# Sheet1.net
KiCad netlist of a schematic drawn in Altium Designer
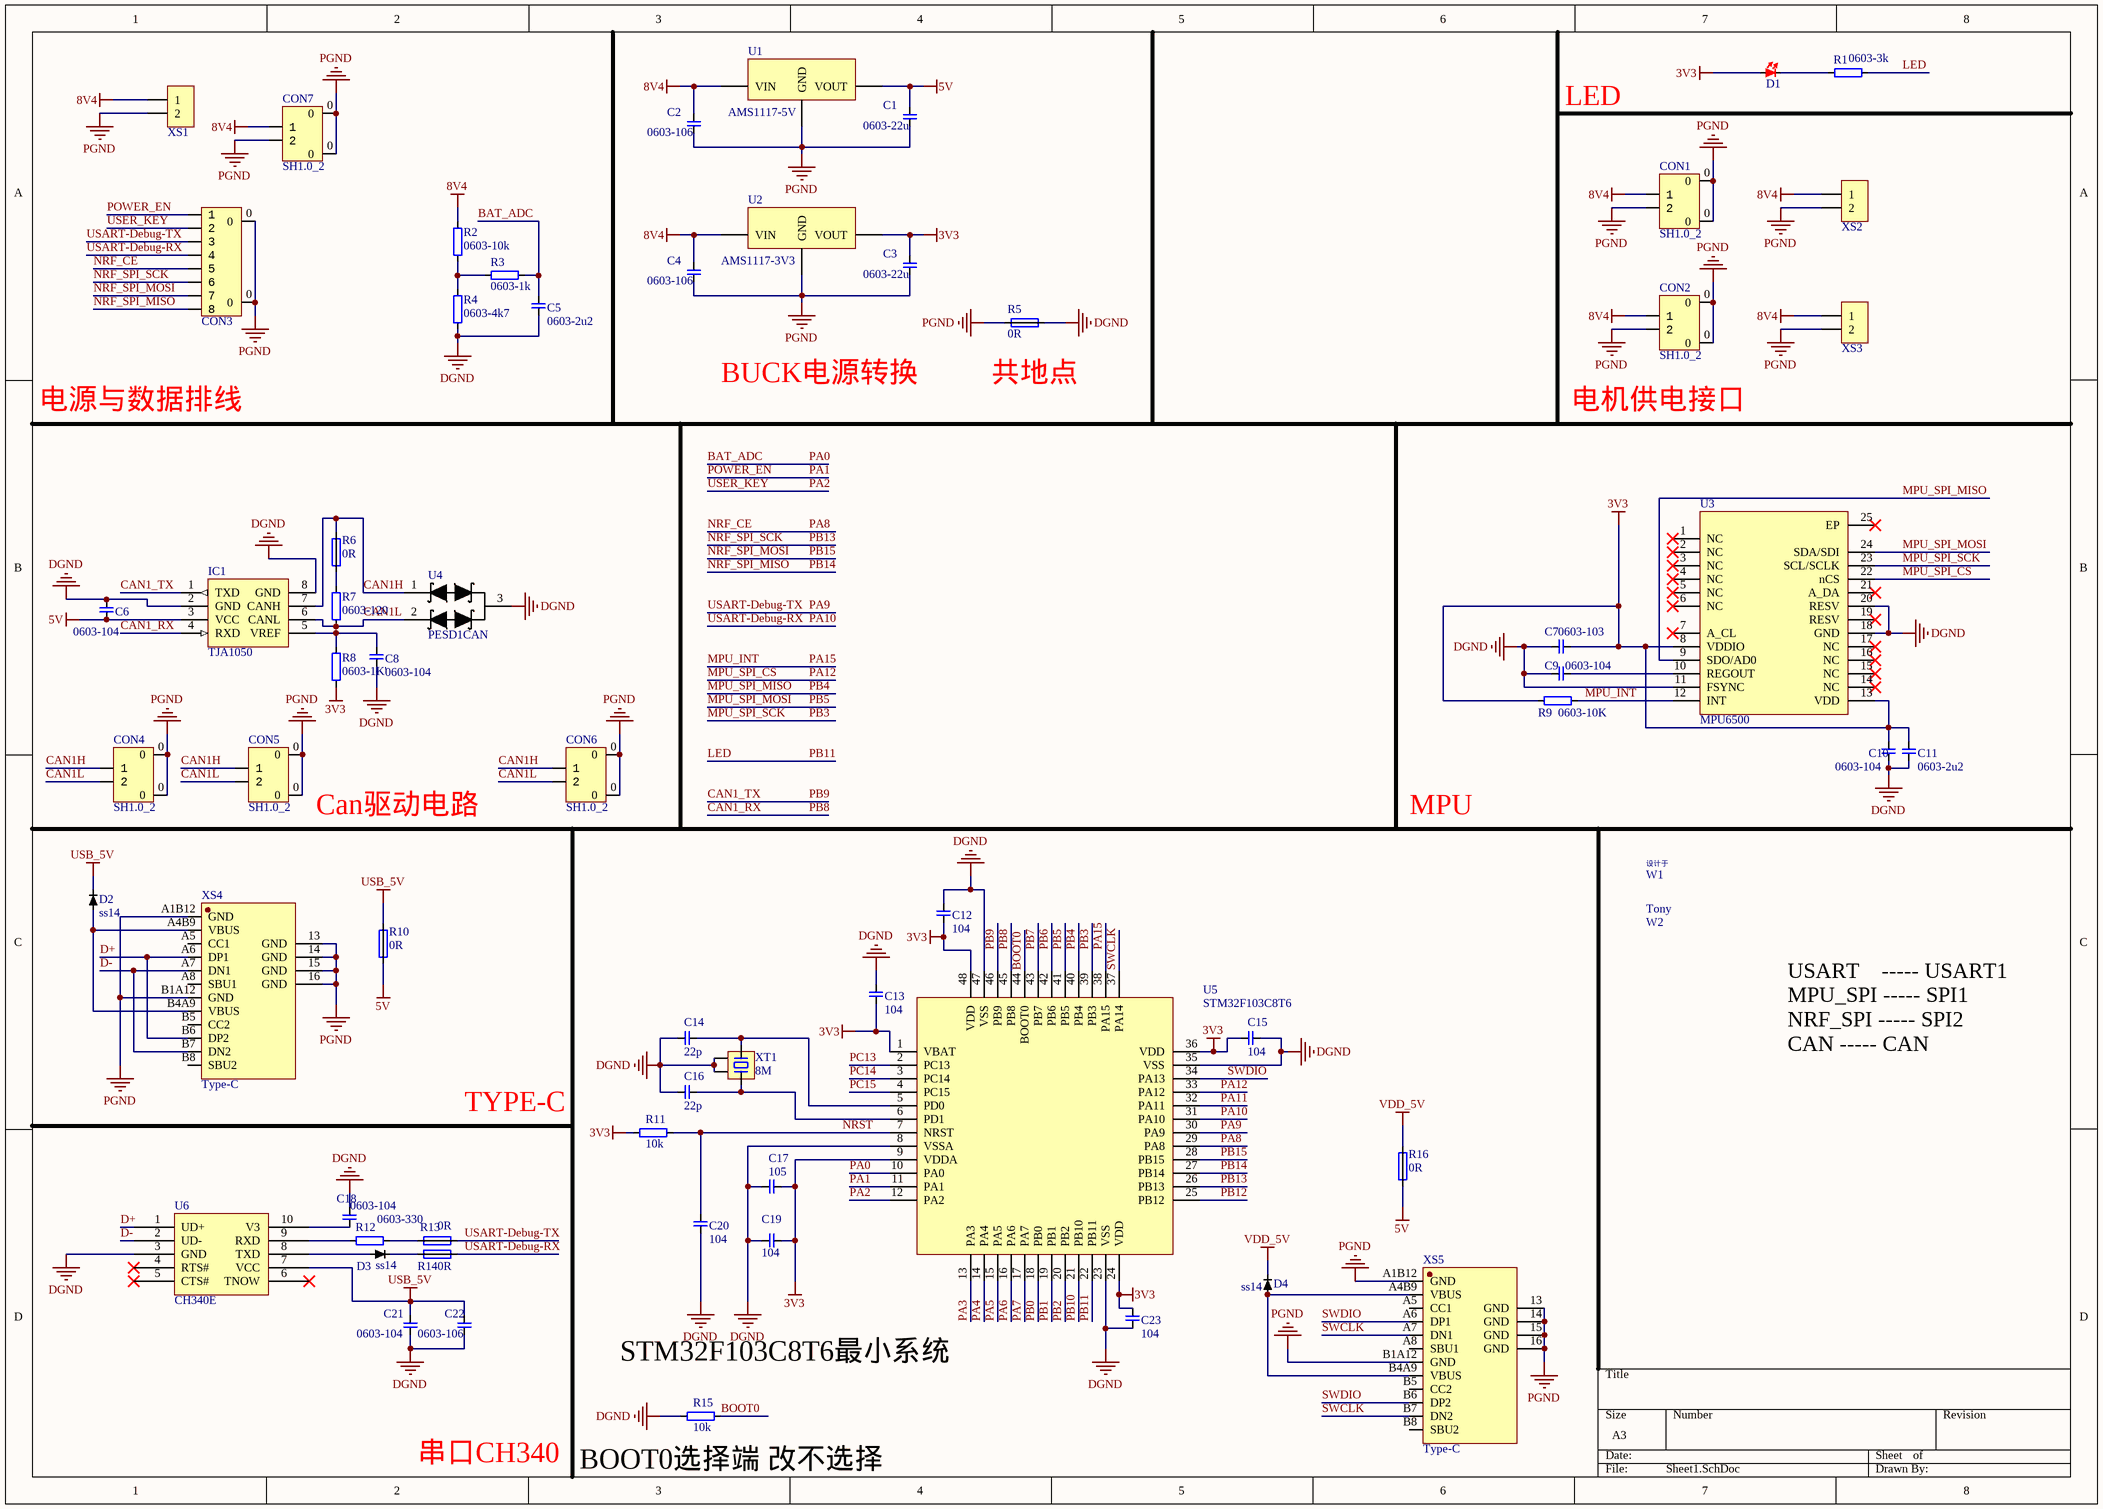
[diagram p0: Sheet1.SchDoc]

(export (version "E")
  (design (tool "Eeschema 10.0.6"))
  (components
    (comp (ref "C1") (value "0603-22u") (footprint "CAP_0603") (libsource (lib "基本元件库") (part "cap")))
    (comp (ref "C2") (value "0603-106") (footprint "CAP_0603") (libsource (lib "基本元件库") (part "cap")))
    (comp (ref "C3") (value "0603-22u") (footprint "CAP_0603") (libsource (lib "基本元件库") (part "cap")))
    (comp (ref "C4") (value "0603-106") (footprint "CAP_0603") (libsource (lib "基本元件库") (part "cap")))
    (comp (ref "C5") (value "0603-2u2") (footprint "CAP_0603") (libsource (lib "基本元件库") (part "cap")))
    (comp (ref "C6") (value "0603-104") (footprint "CAP_0603") (libsource (lib "基本元件库") (part "cap")))
    (comp (ref "C7") (value "0603-103") (footprint "CAP_0603") (libsource (lib "基本元件库") (part "cap")))
    (comp (ref "C8") (value "0603-104") (footprint "CAP_0603") (libsource (lib "基本元件库") (part "cap")))
    (comp (ref "C9") (value "0603-104") (footprint "CAP_0603") (libsource (lib "基本元件库") (part "cap")))
    (comp (ref "C10") (value "0603-104") (footprint "CAP_0603") (libsource (lib "基本元件库") (part "cap")))
    (comp (ref "C11") (value "0603-2u2") (footprint "CAP_0603") (libsource (lib "基本元件库") (part "cap")))
    (comp (ref "C12") (value "104") (footprint "CAP_0603") (libsource (lib "基本元件库") (part "cap")))
    (comp (ref "C13") (value "104") (footprint "CAP_0603") (libsource (lib "基本元件库") (part "cap")))
    (comp (ref "C14") (value "22p") (footprint "CAP_0603") (libsource (lib "基本元件库") (part "cap")))
    (comp (ref "C15") (value "104") (footprint "CAP_0603") (libsource (lib "基本元件库") (part "cap")))
    (comp (ref "C16") (value "22p") (footprint "CAP_0603") (libsource (lib "基本元件库") (part "cap")))
    (comp (ref "C17") (value "105") (footprint "CAP_0603") (libsource (lib "基本元件库") (part "cap")))
    (comp (ref "C18") (value "0603-104") (footprint "CAP_0603") (libsource (lib "基本元件库") (part "cap")))
    (comp (ref "C19") (value "104") (footprint "CAP_0603") (libsource (lib "基本元件库") (part "cap")))
    (comp (ref "C20") (value "104") (footprint "CAP_0603") (libsource (lib "基本元件库") (part "cap")))
    (comp (ref "C21") (value "0603-104") (footprint "CAP_0603") (libsource (lib "基本元件库") (part "cap")))
    (comp (ref "C22") (value "0603-106") (footprint "CAP_0603") (libsource (lib "基本元件库") (part "cap")))
    (comp (ref "C23") (value "104") (footprint "CAP_0603") (libsource (lib "基本元件库") (part "cap")))
    (comp (ref "CON1")
      (value "SH1.0_2")
      (footprint "SH1.0 Vertical 2P")
      (description "SH1.0 座子")
      (libsource (lib "接插件库") (part "SH1.0_2"))
    )
    (comp (ref "CON2")
      (value "SH1.0_2")
      (footprint "SH1.0 Vertical 2P")
      (description "SH1.0 座子")
      (libsource (lib "接插件库") (part "SH1.0_2"))
    )
    (comp (ref "CON3")
      (value "FFC_0.5_8")
      (footprint "FFC_0.5_8")
      (description "FFC")
      (libsource (lib "接插件库") (part "FFC_0.5_8"))
    )
    (comp (ref "CON4")
      (value "SH1.0_2")
      (footprint "SH1.0 Vertical 2P")
      (description "SH1.0 座子")
      (libsource (lib "接插件库") (part "SH1.0_2"))
    )
    (comp (ref "CON5")
      (value "SH1.0_2")
      (footprint "SH1.0 Vertical 2P")
      (description "SH1.0 座子")
      (libsource (lib "接插件库") (part "SH1.0_2"))
    )
    (comp (ref "CON6")
      (value "SH1.0_2")
      (footprint "SH1.0 Vertical 2P")
      (description "SH1.0 座子")
      (libsource (lib "接插件库") (part "SH1.0_2"))
    )
    (comp (ref "CON7")
      (value "SH1.0_2")
      (footprint "SH1.0 Vertical 2P")
      (description "SH1.0 座子")
      (libsource (lib "接插件库") (part "SH1.0_2"))
    )
    (comp (ref "D1") (value "led") (footprint "led0603") (libsource (lib "基本元件库") (part "led")))
    (comp (ref "D2") (value "ss14") (footprint "SOD-323") (libsource (lib "基本元件库") (part "Diode")))
    (comp (ref "D3") (value "ss14") (footprint "SOD-323") (libsource (lib "基本元件库") (part "Diode")))
    (comp (ref "D4") (value "ss14") (footprint "SOD-323") (libsource (lib "基本元件库") (part "Diode")))
    (comp (ref "IC1")
      (value "TJA1050")
      (footprint "SOP8_N")
      (description "CAN总线收发芯片")
      (fields (field (name "版权归属") "源创客"))
      (libsource (lib "IC") (part "TJA1050"))
    )
    (comp (ref "R1") (value "0603-3k") (footprint "RES_0603") (libsource (lib "基本元件库") (part "Res")))
    (comp (ref "R2") (value "0603-10k") (footprint "RES_0603") (libsource (lib "基本元件库") (part "Res")))
    (comp (ref "R3") (value "0603-1k") (footprint "RES_0603") (libsource (lib "基本元件库") (part "Res")))
    (comp (ref "R4") (value "0603-4k7") (footprint "RES_0603") (libsource (lib "基本元件库") (part "Res")))
    (comp (ref "R5") (value "0R") (footprint "RES_0805-SHORT") (libsource (lib "基本元件库") (part "Res-SHORT")))
    (comp (ref "R6") (value "0R") (footprint "RES_0603-SHORT") (libsource (lib "基本元件库") (part "Res-SHORT")))
    (comp (ref "R7") (value "0603-120") (footprint "RES_0603") (libsource (lib "基本元件库") (part "Res")))
    (comp (ref "R8") (value "0603-1K'") (footprint "RES_0603") (libsource (lib "基本元件库") (part "Res")))
    (comp (ref "R9") (value "0603-10K") (footprint "RES_0603") (libsource (lib "基本元件库") (part "Res")))
    (comp (ref "R10") (value "0R") (footprint "RES_0805-SHORT") (libsource (lib "基本元件库") (part "Res-SHORT")))
    (comp (ref "R11") (value "10k") (footprint "RES_0603") (libsource (lib "基本元件库") (part "Res")))
    (comp (ref "R12") (value "0603-330") (footprint "RES_0603") (libsource (lib "基本元件库") (part "Res")))
    (comp (ref "R13") (value "0R") (footprint "RES_0402-SHORT") (libsource (lib "基本元件库") (part "Res-SHORT")))
    (comp (ref "R14") (value "0R") (footprint "RES_0402-SHORT") (libsource (lib "基本元件库") (part "Res-SHORT")))
    (comp (ref "R15") (value "10k") (footprint "RES_0603") (libsource (lib "基本元件库") (part "Res")))
    (comp (ref "R16") (value "0R") (footprint "RES_0805-SHORT") (libsource (lib "基本元件库") (part "Res-SHORT")))
    (comp (ref "U1") (value "AMS1117-5V") (footprint "SOT223") (libsource (lib "SOURCE") (part "AMS1117")))
    (comp (ref "U2") (value "AMS1117-3V3") (footprint "SOT223") (libsource (lib "SOURCE") (part "AMS1117")))
    (comp (ref "U3")
      (value "MPU6500")
      (footprint "QFN-24_3X3")
      (description "六轴传感器")
      (libsource (lib "IC") (part "MPU6500"))
    )
    (comp (ref "U4")
      (value "PESD1CAN")
      (footprint "SOT23-3")
      (description "CAN过压保护,放于外部接口端")
      (libsource (lib "IC") (part "PESD1CAN"))
    )
    (comp (ref "U5")
      (value "STM32F103C8T6")
      (footprint "LQFP48")
      (libsource (lib "MCU") (part "STM32F103C8T6-LCC"))
    )
    (comp (ref "U6")
      (value "CH340E")
      (footprint "MSOP10")
      (description "USB转串口 无外置晶振")
      (libsource (lib "IC") (part "CH340E"))
    )
    (comp (ref "W1") (value "设计于") (footprint "designed by（430-70）") (libsource (lib "丝印库") (part "设计于")))
    (comp (ref "W2") (value "Tony") (footprint "Tony_2(200-70)") (libsource (lib "丝印库") (part "Tony")))
    (comp (ref "XS1")
      (value "HDR-1X2")
      (footprint "15EDGVM-2P")
      (description "2P接插件")
      (fields (field (name "版权归属") "源创客"))
      (libsource (lib "接插件库") (part "Header 2"))
    )
    (comp (ref "XS2")
      (value "HDR-1X2")
      (footprint "HDR2")
      (description "2P接插件")
      (fields (field (name "版权归属") "源创客"))
      (libsource (lib "接插件库") (part "Header 2"))
    )
    (comp (ref "XS3")
      (value "HDR-1X2")
      (footprint "HDR2")
      (description "2P接插件")
      (fields (field (name "版权归属") "源创客"))
      (libsource (lib "接插件库") (part "Header 2"))
    )
    (comp (ref "XS4")
      (value "Type-C")
      (footprint "TypeC-304-16BCP")
      (libsource (lib "接插件库") (part "Type-C母口"))
    )
    (comp (ref "XS5")
      (value "Type-C")
      (footprint "TypeC-304-16BCP")
      (libsource (lib "接插件库") (part "Type-C母口"))
    )
    (comp (ref "XT1") (value "8M") (footprint "SMD3225_4p") (libsource (lib "基本元件库") (part "XTAL-4P")))
  )
  (nets
    (net (code "1") (name "/BAT_ADC") (class "Default")
      (node (ref "C5") (pin "2") (pinfunction "2_2") (pintype "passive"))
      (node (ref "R3") (pin "1") (pinfunction "1_1") (pintype "passive"))
      (node (ref "U5") (pin "10") (pinfunction "PA0_10") (pintype "passive"))
    )
    (net (code "2") (name "/BOOT0") (class "Default")
      (node (ref "R15") (pin "2") (pinfunction "2_2") (pintype "passive"))
      (node (ref "U5") (pin "44") (pinfunction "BOOT0_44") (pintype "passive"))
    )
    (net (code "3") (name "/CAN1H") (class "Default")
      (node (ref "CON4") (pin "1") (pinfunction "1_1") (pintype "passive"))
      (node (ref "CON5") (pin "1") (pinfunction "1_1") (pintype "passive"))
      (node (ref "CON6") (pin "1") (pinfunction "1_1") (pintype "passive"))
      (node (ref "IC1") (pin "7") (pinfunction "CANH_7") (pintype "passive"))
      (node (ref "R6") (pin "1") (pinfunction "1_1") (pintype "passive"))
      (node (ref "U4") (pin "1") (pinfunction "1_1") (pintype "passive"))
    )
    (net (code "4") (name "/CAN1L") (class "Default")
      (node (ref "CON4") (pin "2") (pinfunction "2_2") (pintype "passive"))
      (node (ref "CON5") (pin "2") (pinfunction "2_2") (pintype "passive"))
      (node (ref "CON6") (pin "2") (pinfunction "2_2") (pintype "passive"))
      (node (ref "IC1") (pin "6") (pinfunction "CANL_6") (pintype "passive"))
      (node (ref "R7") (pin "1") (pinfunction "1_1") (pintype "passive"))
      (node (ref "U4") (pin "2") (pinfunction "2_2") (pintype "passive"))
    )
    (net (code "5") (name "/CAN1_RX") (class "Default")
      (node (ref "IC1") (pin "4") (pinfunction "RXD_4") (pintype "input"))
      (node (ref "U5") (pin "45") (pinfunction "PB8_45") (pintype "passive"))
    )
    (net (code "6") (name "/CAN1_TX") (class "Default")
      (node (ref "IC1") (pin "1") (pinfunction "TXD_1") (pintype "output"))
      (node (ref "U5") (pin "46") (pinfunction "PB9_46") (pintype "passive"))
    )
    (net (code "7") (name "/D+") (class "Default")
      (node (ref "U6") (pin "1") (pinfunction "UD+_1") (pintype "passive"))
      (node (ref "XS4") (pin "A6") (pinfunction "DP1_A6") (pintype "passive"))
      (node (ref "XS4") (pin "B6") (pinfunction "DP2_B6") (pintype "passive"))
    )
    (net (code "8") (name "/D-") (class "Default")
      (node (ref "U6") (pin "2") (pinfunction "UD-_2") (pintype "passive"))
      (node (ref "XS4") (pin "A7") (pinfunction "DN1_A7") (pintype "passive"))
      (node (ref "XS4") (pin "B7") (pinfunction "DN2_B7") (pintype "passive"))
    )
    (net (code "9") (name "/LED") (class "Default")
      (node (ref "R1") (pin "2") (pinfunction "2_2") (pintype "passive"))
      (node (ref "U5") (pin "22") (pinfunction "PB11_22") (pintype "passive"))
    )
    (net (code "10") (name "/MPU_INT") (class "Default")
      (node (ref "R9") (pin "2") (pinfunction "2_2") (pintype "passive"))
      (node (ref "U3") (pin "12") (pinfunction "INT_12") (pintype "passive"))
      (node (ref "U5") (pin "38") (pinfunction "PA15_38") (pintype "passive"))
    )
    (net (code "11") (name "/MPU_SPI_CS") (class "Default")
      (node (ref "U3") (pin "22") (pinfunction "nCS_22") (pintype "passive"))
      (node (ref "U5") (pin "33") (pinfunction "PA12_33") (pintype "passive"))
    )
    (net (code "12") (name "/MPU_SPI_MISO") (class "Default")
      (node (ref "U3") (pin "9") (pinfunction "SDO/AD0_9") (pintype "passive"))
      (node (ref "U5") (pin "40") (pinfunction "PB4_40") (pintype "passive"))
    )
    (net (code "13") (name "/MPU_SPI_MOSI") (class "Default")
      (node (ref "U3") (pin "24") (pinfunction "SDA/SDI_24") (pintype "passive"))
      (node (ref "U5") (pin "41") (pinfunction "PB5_41") (pintype "passive"))
    )
    (net (code "14") (name "/MPU_SPI_SCK") (class "Default")
      (node (ref "U3") (pin "23") (pinfunction "SCL/SCLK_23") (pintype "passive"))
      (node (ref "U5") (pin "39") (pinfunction "PB3_39") (pintype "passive"))
    )
    (net (code "15") (name "/NRF_CE") (class "Default")
      (node (ref "CON3") (pin "5") (pinfunction "5_5") (pintype "passive"))
      (node (ref "U5") (pin "29") (pinfunction "PA8_29") (pintype "passive"))
    )
    (net (code "16") (name "/NRF_SPI_MISO") (class "Default")
      (node (ref "CON3") (pin "8") (pinfunction "8_8") (pintype "passive"))
      (node (ref "U5") (pin "27") (pinfunction "PB14_27") (pintype "passive"))
    )
    (net (code "17") (name "/NRF_SPI_MOSI") (class "Default")
      (node (ref "CON3") (pin "7") (pinfunction "7_7") (pintype "passive"))
      (node (ref "U5") (pin "28") (pinfunction "PB15_28") (pintype "passive"))
    )
    (net (code "18") (name "/NRF_SPI_SCK") (class "Default")
      (node (ref "CON3") (pin "6") (pinfunction "6_6") (pintype "passive"))
      (node (ref "U5") (pin "26") (pinfunction "PB13_26") (pintype "passive"))
    )
    (net (code "19") (name "/NRST") (class "Default")
      (node (ref "C20") (pin "1") (pinfunction "1_1") (pintype "passive"))
      (node (ref "R11") (pin "2") (pinfunction "2_2") (pintype "passive"))
      (node (ref "U5") (pin "7") (pinfunction "NRST_7") (pintype "passive"))
    )
    (net (code "20") (name "/PA1") (class "Default")
      (node (ref "CON3") (pin "1") (pinfunction "1_1") (pintype "passive"))
      (node (ref "U5") (pin "11") (pinfunction "PA1_11") (pintype "passive"))
    )
    (net (code "21") (name "/PA2") (class "Default")
      (node (ref "CON3") (pin "2") (pinfunction "2_2") (pintype "passive"))
      (node (ref "U5") (pin "12") (pinfunction "PA2_12") (pintype "passive"))
    )
    (net (code "22") (name "/PA3") (class "Default")
      (node (ref "U5") (pin "13") (pinfunction "PA3_13") (pintype "passive"))
    )
    (net (code "23") (name "/PA4") (class "Default")
      (node (ref "U5") (pin "14") (pinfunction "PA4_14") (pintype "passive"))
    )
    (net (code "24") (name "/PA5") (class "Default")
      (node (ref "U5") (pin "15") (pinfunction "PA5_15") (pintype "passive"))
    )
    (net (code "25") (name "/PA6") (class "Default")
      (node (ref "U5") (pin "16") (pinfunction "PA6_16") (pintype "passive"))
    )
    (net (code "26") (name "/PA7") (class "Default")
      (node (ref "U5") (pin "17") (pinfunction "PA7_17") (pintype "passive"))
    )
    (net (code "27") (name "/PA9") (class "Default")
      (node (ref "CON3") (pin "3") (pinfunction "3_3") (pintype "passive"))
      (node (ref "R13") (pin "2") (pinfunction "2_2") (pintype "passive"))
      (node (ref "U5") (pin "30") (pinfunction "PA9_30") (pintype "passive"))
    )
    (net (code "28") (name "/PA10") (class "Default")
      (node (ref "CON3") (pin "4") (pinfunction "4_4") (pintype "passive"))
      (node (ref "R14") (pin "2") (pinfunction "2_2") (pintype "passive"))
      (node (ref "U5") (pin "31") (pinfunction "PA10_31") (pintype "passive"))
    )
    (net (code "29") (name "/PA11") (class "Default")
      (node (ref "U5") (pin "32") (pinfunction "PA11_32") (pintype "passive"))
    )
    (net (code "30") (name "/PB0") (class "Default")
      (node (ref "U5") (pin "18") (pinfunction "PB0_18") (pintype "passive"))
    )
    (net (code "31") (name "/PB1") (class "Default")
      (node (ref "U5") (pin "19") (pinfunction "PB1_19") (pintype "passive"))
    )
    (net (code "32") (name "/PB2") (class "Default")
      (node (ref "U5") (pin "20") (pinfunction "PB2_20") (pintype "passive"))
    )
    (net (code "33") (name "/PB6") (class "Default")
      (node (ref "U5") (pin "42") (pinfunction "PB6_42") (pintype "passive"))
    )
    (net (code "34") (name "/PB7") (class "Default")
      (node (ref "U5") (pin "43") (pinfunction "PB7_43") (pintype "passive"))
    )
    (net (code "35") (name "/PB10") (class "Default")
      (node (ref "U5") (pin "21") (pinfunction "PB10_21") (pintype "passive"))
    )
    (net (code "36") (name "/PB12") (class "Default")
      (node (ref "U5") (pin "25") (pinfunction "PB12_25") (pintype "passive"))
    )
    (net (code "37") (name "/PC13") (class "Default")
      (node (ref "U5") (pin "2") (pinfunction "PC13_2") (pintype "passive"))
    )
    (net (code "38") (name "/PC14") (class "Default")
      (node (ref "U5") (pin "3") (pinfunction "PC14_3") (pintype "passive"))
    )
    (net (code "39") (name "/PC15") (class "Default")
      (node (ref "U5") (pin "4") (pinfunction "PC15_4") (pintype "passive"))
    )
    (net (code "40") (name "/SWCLK") (class "Default")
      (node (ref "U5") (pin "37") (pinfunction "PA14_37") (pintype "passive"))
      (node (ref "XS5") (pin "A7") (pinfunction "DN1_A7") (pintype "passive"))
      (node (ref "XS5") (pin "B7") (pinfunction "DN2_B7") (pintype "passive"))
    )
    (net (code "41") (name "/SWDIO") (class "Default")
      (node (ref "U5") (pin "34") (pinfunction "PA13_34") (pintype "passive"))
      (node (ref "XS5") (pin "A6") (pinfunction "DP1_A6") (pintype "passive"))
      (node (ref "XS5") (pin "B6") (pinfunction "DP2_B6") (pintype "passive"))
    )
    (net (code "42") (name "3V3") (class "Default")
      (node (ref "C10") (pin "2") (pinfunction "2_2") (pintype "passive"))
      (node (ref "C11") (pin "2") (pinfunction "2_2") (pintype "passive"))
      (node (ref "C12") (pin "2") (pinfunction "2_2") (pintype "passive"))
      (node (ref "C13") (pin "1") (pinfunction "1_1") (pintype "passive"))
      (node (ref "C15") (pin "2") (pinfunction "2_2") (pintype "passive"))
      (node (ref "C17") (pin "2") (pinfunction "2_2") (pintype "passive"))
      (node (ref "C19") (pin "2") (pinfunction "2_2") (pintype "passive"))
      (node (ref "C23") (pin "2") (pinfunction "2_2") (pintype "passive"))
      (node (ref "C3") (pin "2") (pinfunction "2_2") (pintype "passive"))
      (node (ref "C7") (pin "2") (pinfunction "2_2") (pintype "passive"))
      (node (ref "D1") (pin "1") (pintype "passive"))
      (node (ref "R11") (pin "1") (pinfunction "1_1") (pintype "passive"))
      (node (ref "R8") (pin "1") (pinfunction "1_1") (pintype "passive"))
      (node (ref "R9") (pin "1") (pinfunction "1_1") (pintype "passive"))
      (node (ref "U2") (pin "2") (pinfunction "VOUT_2") (pintype "passive"))
      (node (ref "U3") (pin "13") (pinfunction "VDD_13") (pintype "passive"))
      (node (ref "U3") (pin "8") (pinfunction "VDDIO_8") (pintype "passive"))
      (node (ref "U5") (pin "1") (pinfunction "VBAT_1") (pintype "passive"))
      (node (ref "U5") (pin "24") (pinfunction "VDD_24") (pintype "passive"))
      (node (ref "U5") (pin "36") (pinfunction "VDD_36") (pintype "passive"))
      (node (ref "U5") (pin "48") (pinfunction "VDD_48") (pintype "passive"))
      (node (ref "U5") (pin "9") (pinfunction "VDDA_9") (pintype "passive"))
    )
    (net (code "43") (name "5V") (class "Default")
      (node (ref "C1") (pin "2") (pinfunction "2_2") (pintype "passive"))
      (node (ref "C6") (pin "1") (pinfunction "1_1") (pintype "passive"))
      (node (ref "IC1") (pin "3") (pinfunction "VCC_3") (pintype "passive"))
      (node (ref "R10") (pin "1") (pinfunction "1_1") (pintype "passive"))
      (node (ref "R16") (pin "1") (pinfunction "1_1") (pintype "passive"))
      (node (ref "U1") (pin "2") (pinfunction "VOUT_2") (pintype "passive"))
    )
    (net (code "44") (name "8V4") (class "Default")
      (node (ref "C2") (pin "2") (pinfunction "2_2") (pintype "passive"))
      (node (ref "C4") (pin "2") (pinfunction "2_2") (pintype "passive"))
      (node (ref "CON1") (pin "1") (pinfunction "1_1") (pintype "passive"))
      (node (ref "CON2") (pin "1") (pinfunction "1_1") (pintype "passive"))
      (node (ref "CON7") (pin "1") (pinfunction "1_1") (pintype "passive"))
      (node (ref "R2") (pin "2") (pinfunction "2_2") (pintype "passive"))
      (node (ref "U1") (pin "3") (pinfunction "VIN_3") (pintype "passive"))
      (node (ref "U2") (pin "3") (pinfunction "VIN_3") (pintype "passive"))
      (node (ref "XS1") (pin "1") (pinfunction "1_1") (pintype "passive"))
      (node (ref "XS2") (pin "1") (pinfunction "1_1") (pintype "passive"))
      (node (ref "XS3") (pin "1") (pinfunction "1_1") (pintype "passive"))
    )
    (net (code "45") (name "DGND") (class "Default")
      (node (ref "C10") (pin "1") (pinfunction "1_1") (pintype "passive"))
      (node (ref "C11") (pin "1") (pinfunction "1_1") (pintype "passive"))
      (node (ref "C12") (pin "1") (pinfunction "1_1") (pintype "passive"))
      (node (ref "C13") (pin "2") (pinfunction "2_2") (pintype "passive"))
      (node (ref "C14") (pin "2") (pinfunction "2_2") (pintype "passive"))
      (node (ref "C15") (pin "1") (pinfunction "1_1") (pintype "passive"))
      (node (ref "C16") (pin "2") (pinfunction "2_2") (pintype "passive"))
      (node (ref "C17") (pin "1") (pinfunction "1_1") (pintype "passive"))
      (node (ref "C18") (pin "2") (pinfunction "2_2") (pintype "passive"))
      (node (ref "C19") (pin "1") (pinfunction "1_1") (pintype "passive"))
      (node (ref "C20") (pin "2") (pinfunction "2_2") (pintype "passive"))
      (node (ref "C21") (pin "1") (pinfunction "1_1") (pintype "passive"))
      (node (ref "C22") (pin "1") (pinfunction "1_1") (pintype "passive"))
      (node (ref "C23") (pin "1") (pinfunction "1_1") (pintype "passive"))
      (node (ref "C5") (pin "1") (pinfunction "1_1") (pintype "passive"))
      (node (ref "C6") (pin "2") (pinfunction "2_2") (pintype "passive"))
      (node (ref "C7") (pin "1") (pinfunction "1_1") (pintype "passive"))
      (node (ref "C8") (pin "1") (pinfunction "1_1") (pintype "passive"))
      (node (ref "C9") (pin "1") (pinfunction "1_1") (pintype "passive"))
      (node (ref "IC1") (pin "2") (pinfunction "GND_2") (pintype "passive"))
      (node (ref "IC1") (pin "8") (pinfunction "GND_8") (pintype "passive"))
      (node (ref "R15") (pin "1") (pinfunction "1_1") (pintype "passive"))
      (node (ref "R4") (pin "1") (pinfunction "1_1") (pintype "passive"))
      (node (ref "R5") (pin "1") (pinfunction "1_1") (pintype "passive"))
      (node (ref "U3") (pin "11") (pinfunction "FSYNC_11") (pintype "passive"))
      (node (ref "U3") (pin "18") (pinfunction "GND_18") (pintype "passive"))
      (node (ref "U3") (pin "20") (pinfunction "RESV_20") (pintype "passive"))
      (node (ref "U4") (pin "3") (pinfunction "3_3") (pintype "passive"))
      (node (ref "U5") (pin "23") (pinfunction "VSS_23") (pintype "passive"))
      (node (ref "U5") (pin "35") (pinfunction "VSS_35") (pintype "passive"))
      (node (ref "U5") (pin "47") (pinfunction "VSS_47") (pintype "passive"))
      (node (ref "U5") (pin "8") (pinfunction "VSSA_8") (pintype "passive"))
      (node (ref "U6") (pin "3") (pinfunction "GND_3") (pintype "passive"))
      (node (ref "XT1") (pin "2") (pinfunction "GND_2") (pintype "passive"))
      (node (ref "XT1") (pin "4") (pinfunction "GND_4") (pintype "passive"))
    )
    (net (code "46") (name "Net-(D1-Pad2)") (class "Default")
      (node (ref "D1") (pin "2") (pintype "passive"))
      (node (ref "R1") (pin "1") (pinfunction "1_1") (pintype "passive"))
    )
    (net (code "47") (name "Net-(D2-Pad1)") (class "Default")
      (node (ref "D2") (pin "1") (pintype "passive"))
      (node (ref "XS4") (pin "A4B9") (pinfunction "VBUS_A4B9") (pintype "passive"))
      (node (ref "XS4") (pin "B4A9") (pinfunction "VBUS_B4A9") (pintype "passive"))
    )
    (net (code "48") (name "Net-(D3-Pad2)") (class "Default")
      (node (ref "D3") (pin "2") (pintype "passive"))
      (node (ref "R14") (pin "1") (pinfunction "1_1") (pintype "passive"))
    )
    (net (code "49") (name "Net-(D4-Pad1)") (class "Default")
      (node (ref "D4") (pin "1") (pintype "passive"))
      (node (ref "XS5") (pin "A4B9") (pinfunction "VBUS_A4B9") (pintype "passive"))
      (node (ref "XS5") (pin "B4A9") (pinfunction "VBUS_B4A9") (pintype "passive"))
    )
    (net (code "50") (name "Net-(IC1-VREF)") (class "Default")
      (node (ref "C8") (pin "2") (pinfunction "2_2") (pintype "passive"))
      (node (ref "IC1") (pin "5") (pinfunction "VREF_5") (pintype "passive"))
      (node (ref "R8") (pin "2") (pinfunction "2_2") (pintype "passive"))
    )
    (net (code "51") (name "Net-(R2-Pad1)") (class "Default")
      (node (ref "R2") (pin "1") (pinfunction "1_1") (pintype "passive"))
      (node (ref "R3") (pin "2") (pinfunction "2_2") (pintype "passive"))
      (node (ref "R4") (pin "2") (pinfunction "2_2") (pintype "passive"))
    )
    (net (code "52") (name "Net-(R6-Pad2)") (class "Default")
      (node (ref "R6") (pin "2") (pinfunction "2_2") (pintype "passive"))
      (node (ref "R7") (pin "2") (pinfunction "2_2") (pintype "passive"))
    )
    (net (code "53") (name "Net-(R12-Pad2)") (class "Default")
      (node (ref "R12") (pin "2") (pinfunction "2_2") (pintype "passive"))
      (node (ref "R13") (pin "1") (pinfunction "1_1") (pintype "passive"))
    )
    (net (code "54") (name "Net-(U3-REGOUT)") (class "Default")
      (node (ref "C9") (pin "2") (pinfunction "2_2") (pintype "passive"))
      (node (ref "U3") (pin "10") (pinfunction "REGOUT_10") (pintype "passive"))
    )
    (net (code "55") (name "Net-(U5-PD0)") (class "Default")
      (node (ref "C14") (pin "1") (pinfunction "1_1") (pintype "passive"))
      (node (ref "U5") (pin "5") (pinfunction "PD0_5") (pintype "passive"))
      (node (ref "XT1") (pin "1") (pinfunction "1_1") (pintype "passive"))
    )
    (net (code "56") (name "Net-(U5-PD1)") (class "Default")
      (node (ref "C16") (pin "1") (pinfunction "1_1") (pintype "passive"))
      (node (ref "U5") (pin "6") (pinfunction "PD1_6") (pintype "passive"))
      (node (ref "XT1") (pin "3") (pinfunction "3_3") (pintype "passive"))
    )
    (net (code "57") (name "Net-(U6-RXD)") (class "Default")
      (node (ref "R12") (pin "1") (pinfunction "1_1") (pintype "passive"))
      (node (ref "U6") (pin "9") (pinfunction "RXD_9") (pintype "passive"))
    )
    (net (code "58") (name "Net-(U6-TXD)") (class "Default")
      (node (ref "D3") (pin "1") (pintype "passive"))
      (node (ref "U6") (pin "8") (pinfunction "TXD_8") (pintype "passive"))
    )
    (net (code "59") (name "Net-(U6-V3)") (class "Default")
      (node (ref "C18") (pin "1") (pinfunction "1_1") (pintype "passive"))
      (node (ref "U6") (pin "10") (pinfunction "V3_10") (pintype "passive"))
    )
    (net (code "60") (name "PGND") (class "Default")
      (node (ref "C1") (pin "1") (pinfunction "1_1") (pintype "passive"))
      (node (ref "C2") (pin "1") (pinfunction "1_1") (pintype "passive"))
      (node (ref "C3") (pin "1") (pinfunction "1_1") (pintype "passive"))
      (node (ref "C4") (pin "1") (pinfunction "1_1") (pintype "passive"))
      (node (ref "CON1") (pin "0") (pinfunction "0_0") (pintype "passive"))
      (node (ref "CON1") (pin "2") (pinfunction "2_2") (pintype "passive"))
      (node (ref "CON2") (pin "0") (pinfunction "0_0") (pintype "passive"))
      (node (ref "CON2") (pin "2") (pinfunction "2_2") (pintype "passive"))
      (node (ref "CON3") (pin "0") (pinfunction "0_0") (pintype "passive"))
      (node (ref "CON4") (pin "0") (pinfunction "0_0") (pintype "passive"))
      (node (ref "CON5") (pin "0") (pinfunction "0_0") (pintype "passive"))
      (node (ref "CON6") (pin "0") (pinfunction "0_0") (pintype "passive"))
      (node (ref "CON7") (pin "0") (pinfunction "0_0") (pintype "passive"))
      (node (ref "CON7") (pin "2") (pinfunction "2_2") (pintype "passive"))
      (node (ref "R5") (pin "2") (pinfunction "2_2") (pintype "passive"))
      (node (ref "U1") (pin "1") (pinfunction "GND_1") (pintype "passive"))
      (node (ref "U2") (pin "1") (pinfunction "GND_1") (pintype "passive"))
      (node (ref "XS1") (pin "2") (pinfunction "2_2") (pintype "passive"))
      (node (ref "XS2") (pin "2") (pinfunction "2_2") (pintype "passive"))
      (node (ref "XS3") (pin "2") (pinfunction "2_2") (pintype "passive"))
      (node (ref "XS4") (pin "13") (pinfunction "GND_13") (pintype "passive"))
      (node (ref "XS4") (pin "14") (pinfunction "GND_14") (pintype "passive"))
      (node (ref "XS4") (pin "15") (pinfunction "GND_15") (pintype "passive"))
      (node (ref "XS4") (pin "16") (pinfunction "GND_16") (pintype "passive"))
      (node (ref "XS4") (pin "A1B12") (pinfunction "GND_A1B12") (pintype "passive"))
      (node (ref "XS4") (pin "B1A12") (pinfunction "GND_B1A12") (pintype "passive"))
      (node (ref "XS5") (pin "13") (pinfunction "GND_13") (pintype "passive"))
      (node (ref "XS5") (pin "14") (pinfunction "GND_14") (pintype "passive"))
      (node (ref "XS5") (pin "15") (pinfunction "GND_15") (pintype "passive"))
      (node (ref "XS5") (pin "16") (pinfunction "GND_16") (pintype "passive"))
      (node (ref "XS5") (pin "A1B12") (pinfunction "GND_A1B12") (pintype "passive"))
      (node (ref "XS5") (pin "B1A12") (pinfunction "GND_B1A12") (pintype "passive"))
    )
    (net (code "61") (name "USB_5V") (class "Default")
      (node (ref "C21") (pin "2") (pinfunction "2_2") (pintype "passive"))
      (node (ref "C22") (pin "2") (pinfunction "2_2") (pintype "passive"))
      (node (ref "D2") (pin "2") (pintype "passive"))
      (node (ref "R10") (pin "2") (pinfunction "2_2") (pintype "passive"))
      (node (ref "U6") (pin "7") (pinfunction "VCC_7") (pintype "passive"))
    )
    (net (code "62") (name "VDD_5V") (class "Default")
      (node (ref "D4") (pin "2") (pintype "passive"))
      (node (ref "R16") (pin "2") (pinfunction "2_2") (pintype "passive"))
    )
    (net (code "63") (name "unconnected-(U3-A_CL-Pad7)") (class "Default")
      (node (ref "U3") (pin "7") (pinfunction "A_CL_7") (pintype "passive+no_connect"))
    )
    (net (code "64") (name "unconnected-(U3-A_DA-Pad21)") (class "Default")
      (node (ref "U3") (pin "21") (pinfunction "A_DA_21") (pintype "passive+no_connect"))
    )
    (net (code "65") (name "unconnected-(U3-EP-Pad25)") (class "Default")
      (node (ref "U3") (pin "25") (pinfunction "EP_25") (pintype "passive+no_connect"))
    )
    (net (code "66") (name "unconnected-(U3-NC-Pad1)") (class "Default")
      (node (ref "U3") (pin "1") (pinfunction "NC_1") (pintype "passive+no_connect"))
    )
    (net (code "67") (name "unconnected-(U3-NC-Pad2)") (class "Default")
      (node (ref "U3") (pin "2") (pinfunction "NC_2") (pintype "passive+no_connect"))
    )
    (net (code "68") (name "unconnected-(U3-NC-Pad3)") (class "Default")
      (node (ref "U3") (pin "3") (pinfunction "NC_3") (pintype "passive+no_connect"))
    )
    (net (code "69") (name "unconnected-(U3-NC-Pad4)") (class "Default")
      (node (ref "U3") (pin "4") (pinfunction "NC_4") (pintype "passive+no_connect"))
    )
    (net (code "70") (name "unconnected-(U3-NC-Pad5)") (class "Default")
      (node (ref "U3") (pin "5") (pinfunction "NC_5") (pintype "passive+no_connect"))
    )
    (net (code "71") (name "unconnected-(U3-NC-Pad6)") (class "Default")
      (node (ref "U3") (pin "6") (pinfunction "NC_6") (pintype "passive+no_connect"))
    )
    (net (code "72") (name "unconnected-(U3-NC-Pad14)") (class "Default")
      (node (ref "U3") (pin "14") (pinfunction "NC_14") (pintype "passive+no_connect"))
    )
    (net (code "73") (name "unconnected-(U3-NC-Pad15)") (class "Default")
      (node (ref "U3") (pin "15") (pinfunction "NC_15") (pintype "passive+no_connect"))
    )
    (net (code "74") (name "unconnected-(U3-NC-Pad16)") (class "Default")
      (node (ref "U3") (pin "16") (pinfunction "NC_16") (pintype "passive+no_connect"))
    )
    (net (code "75") (name "unconnected-(U3-NC-Pad17)") (class "Default")
      (node (ref "U3") (pin "17") (pinfunction "NC_17") (pintype "passive+no_connect"))
    )
    (net (code "76") (name "unconnected-(U3-RESV-Pad19)") (class "Default")
      (node (ref "U3") (pin "19") (pinfunction "RESV_19") (pintype "passive+no_connect"))
    )
    (net (code "77") (name "unconnected-(U6-CTS#-Pad5)") (class "Default")
      (node (ref "U6") (pin "5") (pinfunction "CTS#_5") (pintype "passive+no_connect"))
    )
    (net (code "78") (name "unconnected-(U6-RTS#-Pad4)") (class "Default")
      (node (ref "U6") (pin "4") (pinfunction "RTS#_4") (pintype "passive+no_connect"))
    )
    (net (code "79") (name "unconnected-(U6-TNOW-Pad6)") (class "Default")
      (node (ref "U6") (pin "6") (pinfunction "TNOW_6") (pintype "passive+no_connect"))
    )
    (net (code "80") (name "unconnected-(XS4-CC1-PadA5)") (class "Default")
      (node (ref "XS4") (pin "A5") (pinfunction "CC1_A5") (pintype "passive"))
    )
    (net (code "81") (name "unconnected-(XS4-CC2-PadB5)") (class "Default")
      (node (ref "XS4") (pin "B5") (pinfunction "CC2_B5") (pintype "passive"))
    )
    (net (code "82") (name "unconnected-(XS4-SBU1-PadA8)") (class "Default")
      (node (ref "XS4") (pin "A8") (pinfunction "SBU1_A8") (pintype "passive"))
    )
    (net (code "83") (name "unconnected-(XS4-SBU2-PadB8)") (class "Default")
      (node (ref "XS4") (pin "B8") (pinfunction "SBU2_B8") (pintype "passive"))
    )
    (net (code "84") (name "unconnected-(XS5-CC1-PadA5)") (class "Default")
      (node (ref "XS5") (pin "A5") (pinfunction "CC1_A5") (pintype "passive"))
    )
    (net (code "85") (name "unconnected-(XS5-CC2-PadB5)") (class "Default")
      (node (ref "XS5") (pin "B5") (pinfunction "CC2_B5") (pintype "passive"))
    )
    (net (code "86") (name "unconnected-(XS5-SBU1-PadA8)") (class "Default")
      (node (ref "XS5") (pin "A8") (pinfunction "SBU1_A8") (pintype "passive"))
    )
    (net (code "87") (name "unconnected-(XS5-SBU2-PadB8)") (class "Default")
      (node (ref "XS5") (pin "B8") (pinfunction "SBU2_B8") (pintype "passive"))
    )
  )
)
